# DSO_ADC.net
KiCad netlist of a schematic drawn in Altium Designer
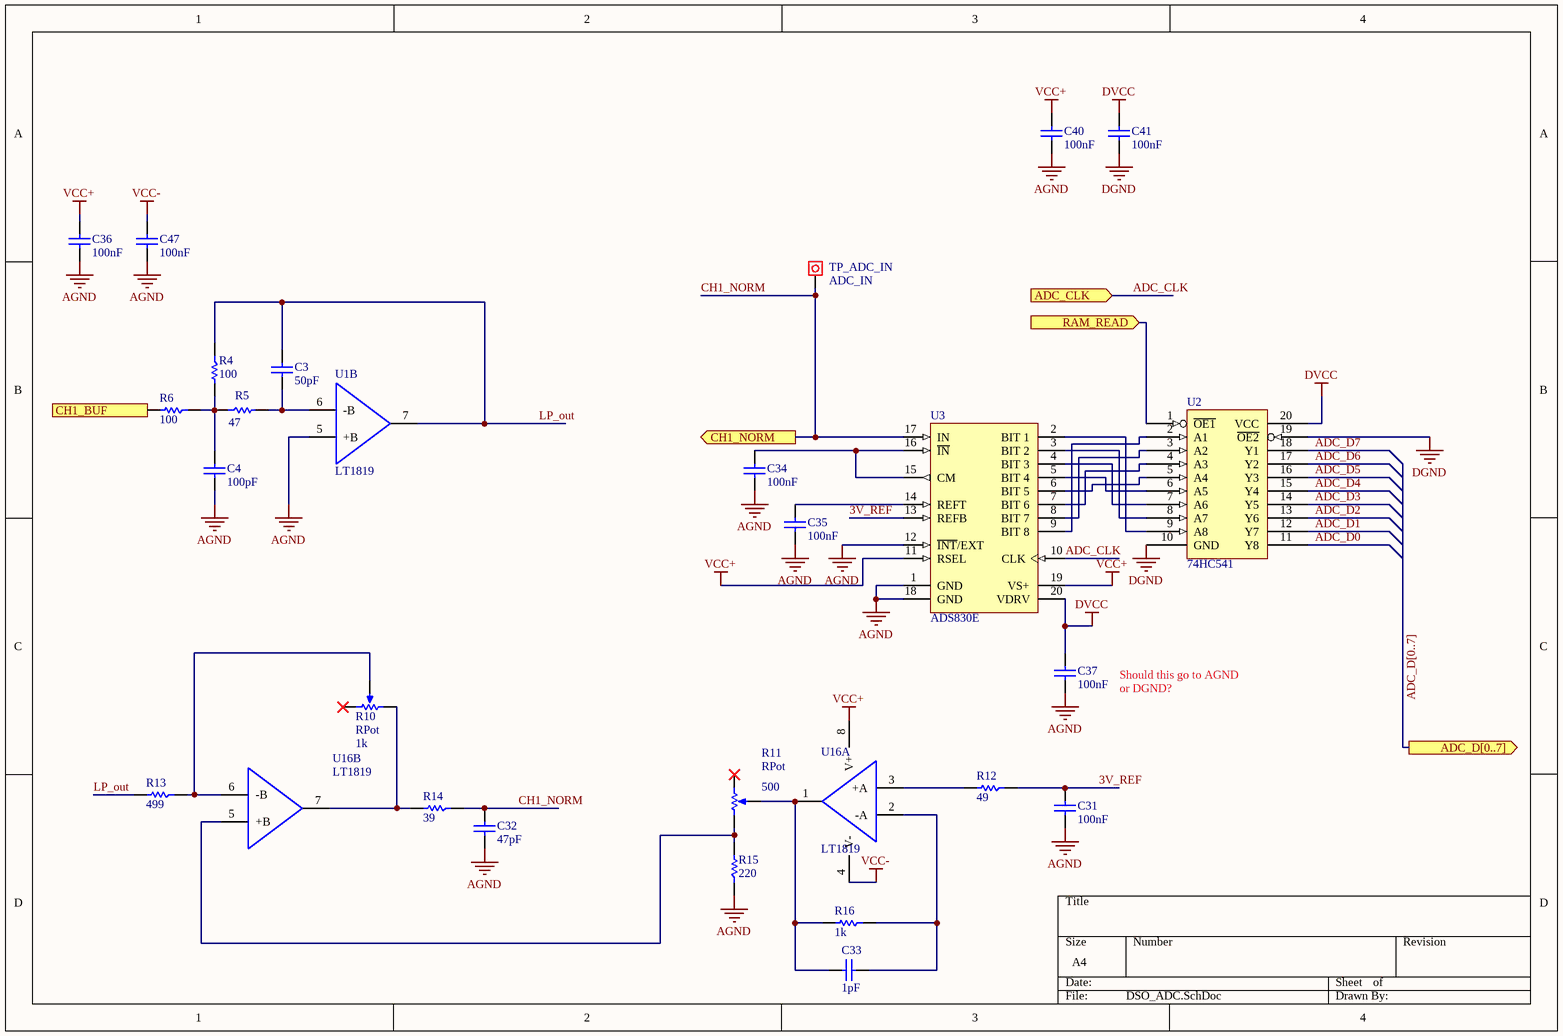
[diagram p0: DSO_ADC.SchDoc]

(export (version "E")
  (design (tool "Eeschema 10.0.6"))
  (components
    (comp (ref "C3")
      (value "50pF")
      (footprint "0805C")
      (description "Capacitor")
      (fields (field (name "REVIEWED BY") "RM - 2018/08/05"))
      (libsource (lib "DSO") (part "C"))
    )
    (comp (ref "C4")
      (value "100pF")
      (footprint "0805C")
      (description "Capacitor")
      (fields (field (name "REVIEWED BY") "RM - 2018/08/05"))
      (libsource (lib "DSO") (part "C"))
    )
    (comp (ref "C31")
      (value "100nF")
      (footprint "0805C")
      (description "Capacitor")
      (fields (field (name "REVIEWED BY") "RM - 2018/08/05"))
      (libsource (lib "DSO") (part "C"))
    )
    (comp (ref "C32")
      (value "47pF")
      (footprint "0805C")
      (description "Capacitor")
      (fields (field (name "REVIEWED BY") "RM - 2018/08/05"))
      (libsource (lib "DSO") (part "C"))
    )
    (comp (ref "C33")
      (value "1pF")
      (footprint "0805C")
      (description "Capacitor")
      (fields (field (name "REVIEWED BY") "RM - 2018/08/05"))
      (libsource (lib "DSO") (part "C"))
    )
    (comp (ref "C34")
      (value "100nF")
      (footprint "0805C")
      (description "Capacitor")
      (fields (field (name "REVIEWED BY") "RM - 2018/08/05"))
      (libsource (lib "DSO") (part "C"))
    )
    (comp (ref "C35")
      (value "100nF")
      (footprint "0805C")
      (description "Capacitor")
      (fields (field (name "REVIEWED BY") "RM - 2018/08/05"))
      (libsource (lib "DSO") (part "C"))
    )
    (comp (ref "C36")
      (value "100nF")
      (footprint "0805C")
      (description "Capacitor")
      (fields (field (name "REVIEWED BY") "RM - 2018/08/05"))
      (libsource (lib "DSO") (part "C"))
    )
    (comp (ref "C37")
      (value "100nF")
      (footprint "0805C")
      (description "Capacitor")
      (fields (field (name "REVIEWED BY") "RM - 2018/08/05"))
      (libsource (lib "DSO") (part "C"))
    )
    (comp (ref "C40")
      (value "100nF")
      (footprint "0805C")
      (description "Capacitor")
      (fields (field (name "REVIEWED BY") "RM - 2018/08/05"))
      (libsource (lib "DSO") (part "C"))
    )
    (comp (ref "C41")
      (value "100nF")
      (footprint "0805C")
      (description "Capacitor")
      (fields (field (name "REVIEWED BY") "RM - 2018/08/05"))
      (libsource (lib "DSO") (part "C"))
    )
    (comp (ref "C47")
      (value "100nF")
      (footprint "0805C")
      (description "Capacitor")
      (fields (field (name "REVIEWED BY") "RM - 2018/08/05"))
      (libsource (lib "DSO") (part "C"))
    )
    (comp (ref "R4")
      (value "100")
      (footprint "0805")
      (description "Resistor")
      (fields (field (name "REVIEWED BY") "RM - 2018/08/05"))
      (libsource (lib "DSO") (part "R"))
    )
    (comp (ref "R5")
      (value "47")
      (footprint "0805")
      (description "Resistor")
      (fields (field (name "REVIEWED BY") "RM - 2018/08/05"))
      (libsource (lib "DSO") (part "R"))
    )
    (comp (ref "R6")
      (value "100")
      (footprint "0805")
      (description "Resistor")
      (fields (field (name "REVIEWED BY") "RM - 2018/08/05"))
      (libsource (lib "DSO") (part "R"))
    )
    (comp (ref "R10")
      (value "RPot")
      (footprint "VR5")
      (description "Potentiometer")
      (fields (field (name "ALTIUM_VALUE") "1k") (field (name "PUBLISHER") "Altium Limited"))
      (libsource (lib "DSO") (part "RPot"))
    )
    (comp (ref "R11")
      (value "RPot")
      (footprint "VR5")
      (description "Potentiometer")
      (fields (field (name "ALTIUM_VALUE") "500") (field (name "PUBLISHER") "Altium Limited"))
      (libsource (lib "DSO") (part "RPot"))
    )
    (comp (ref "R12")
      (value "49")
      (footprint "0805")
      (description "Resistor")
      (fields (field (name "REVIEWED BY") "RM - 2018/08/05"))
      (libsource (lib "DSO") (part "R"))
    )
    (comp (ref "R13")
      (value "499")
      (footprint "0805")
      (description "Resistor")
      (fields (field (name "REVIEWED BY") "RM - 2018/08/05"))
      (libsource (lib "DSO") (part "R"))
    )
    (comp (ref "R14")
      (value "39")
      (footprint "0805")
      (description "Resistor")
      (fields (field (name "REVIEWED BY") "RM - 2018/08/05"))
      (libsource (lib "DSO") (part "R"))
    )
    (comp (ref "R15")
      (value "220")
      (footprint "0805")
      (description "Resistor")
      (fields (field (name "REVIEWED BY") "RM - 2018/08/05"))
      (libsource (lib "DSO") (part "R"))
    )
    (comp (ref "R16")
      (value "1k")
      (footprint "0805")
      (description "Resistor")
      (fields (field (name "REVIEWED BY") "RM - 2018/08/05"))
      (libsource (lib "DSO") (part "R"))
    )
    (comp (ref "TP_ADC_IN")
      (value "ADC_IN")
      (footprint "Testpoin")
      (description "Pad")
      (fields (field (name "Comment") "INPUT"))
      (libsource (lib "DSO") (part "Test Point"))
    )
    (comp (ref "U1")
      (value "LT1819")
      (footprint "SOIC-8")
      (description "OpAmp High Frequency Dual")
      (fields (field (name "REVIEWED BY") "RM - 2018/08/05"))
      (libsource (lib "DSO") (part "LT1819"))
    )
    (comp (ref "U2")
      (value "74HC541")
      (footprint "SOT163-1_N")
      (description "(ADV) Octal Buffer, Line Driver")
      (fields (field (name "REVIEWED BY") "RM - 2018/08/05"))
      (libsource (lib "DSO") (part "74HC541"))
    )
    (comp (ref "U3")
      (value "ADS830E")
      (footprint "TI-DBQ20_L")
      (fields (field (name "REVIEWED BY") "RM - 2018/08/05"))
      (libsource (lib "DSO") (part "ADS830E"))
    )
    (comp (ref "U16")
      (value "LT1819")
      (footprint "SOIC-8")
      (description "OpAmp High Frequency Dual")
      (fields (field (name "REVIEWED BY") "RM - 2018/08/05"))
      (libsource (lib "DSO") (part "LT1819"))
    )
  )
  (nets
    (net (code "1") (name "/3V_REF") (class "Default")
      (node (ref "C31") (pin "1") (pinfunction "1_1") (pintype "passive"))
      (node (ref "R12") (pin "1") (pintype "passive"))
      (node (ref "U3") (pin "13") (pinfunction "REFB_13") (pintype "input"))
    )
    (net (code "2") (name "/ADC_CLK") (class "Default")
      (node (ref "U3") (pin "10") (pinfunction "CLK_10") (pintype "input"))
    )
    (net (code "3") (name "/ADC_D0") (class "Default")
      (node (ref "U2") (pin "11") (pinfunction "Y8_11") (pintype "tri_state"))
    )
    (net (code "4") (name "/ADC_D1") (class "Default")
      (node (ref "U2") (pin "12") (pinfunction "Y7_12") (pintype "tri_state"))
    )
    (net (code "5") (name "/ADC_D2") (class "Default")
      (node (ref "U2") (pin "13") (pinfunction "Y6_13") (pintype "tri_state"))
    )
    (net (code "6") (name "/ADC_D3") (class "Default")
      (node (ref "U2") (pin "14") (pinfunction "Y5_14") (pintype "tri_state"))
    )
    (net (code "7") (name "/ADC_D4") (class "Default")
      (node (ref "U2") (pin "15") (pinfunction "Y4_15") (pintype "tri_state"))
    )
    (net (code "8") (name "/ADC_D5") (class "Default")
      (node (ref "U2") (pin "16") (pinfunction "Y3_16") (pintype "tri_state"))
    )
    (net (code "9") (name "/ADC_D6") (class "Default")
      (node (ref "U2") (pin "17") (pinfunction "Y2_17") (pintype "tri_state"))
    )
    (net (code "10") (name "/ADC_D7") (class "Default")
      (node (ref "U2") (pin "18") (pinfunction "Y1_18") (pintype "tri_state"))
    )
    (net (code "12") (name "/CH1_BUF") (class "Default") (node (ref "R6") (pin "2") (pintype "passive")))
    (net (code "13") (name "/CH1_NORM") (class "Default")
      (node (ref "C32") (pin "1") (pinfunction "1_1") (pintype "passive"))
      (node (ref "R14") (pin "1") (pintype "passive"))
      (node (ref "TP_ADC_IN") (pin "1") (pintype "passive"))
      (node (ref "U3") (pin "17") (pinfunction "IN_17") (pintype "input"))
    )
    (net (code "14") (name "/LP_out") (class "Default")
      (node (ref "C3") (pin "1") (pinfunction "1_1") (pintype "passive"))
      (node (ref "R13") (pin "2") (pintype "passive"))
      (node (ref "R4") (pin "1") (pintype "passive"))
      (node (ref "U1") (pin "7") (pinfunction "OUTB_7") (pintype "passive"))
    )
    (net (code "15") (name "/RAM_READ") (class "Default")
      (node (ref "U2") (pin "1") (pinfunction "~{OE1}_1") (pintype "input"))
    )
    (net (code "16") (name "AGND") (class "Default")
      (node (ref "C31") (pin "2") (pinfunction "2_2") (pintype "passive"))
      (node (ref "C32") (pin "2") (pinfunction "2_2") (pintype "passive"))
      (node (ref "C34") (pin "2") (pinfunction "2_2") (pintype "passive"))
      (node (ref "C35") (pin "2") (pinfunction "2_2") (pintype "passive"))
      (node (ref "C36") (pin "2") (pinfunction "2_2") (pintype "passive"))
      (node (ref "C37") (pin "1") (pinfunction "1_1") (pintype "passive"))
      (node (ref "C4") (pin "2") (pinfunction "2_2") (pintype "passive"))
      (node (ref "C40") (pin "2") (pinfunction "2_2") (pintype "passive"))
      (node (ref "C47") (pin "2") (pinfunction "2_2") (pintype "passive"))
      (node (ref "R15") (pin "1") (pintype "passive"))
      (node (ref "U1") (pin "5") (pinfunction "+B_5") (pintype "passive"))
      (node (ref "U3") (pin "1") (pinfunction "GND_1") (pintype "power_in"))
      (node (ref "U3") (pin "12") (pinfunction "~{INT}/EXT_12") (pintype "input"))
      (node (ref "U3") (pin "18") (pinfunction "GND_18") (pintype "power_in"))
    )
    (net (code "17") (name "DGND") (class "Default")
      (node (ref "C41") (pin "2") (pinfunction "2_2") (pintype "passive"))
      (node (ref "U2") (pin "10") (pinfunction "GND_10") (pintype "power_in"))
      (node (ref "U2") (pin "19") (pinfunction "~{OE2}_19") (pintype "input"))
    )
    (net (code "18") (name "DVCC") (class "Default")
      (node (ref "C37") (pin "2") (pinfunction "2_2") (pintype "passive"))
      (node (ref "C41") (pin "1") (pinfunction "1_1") (pintype "passive"))
      (node (ref "U2") (pin "20") (pinfunction "VCC_20") (pintype "power_in"))
      (node (ref "U3") (pin "20") (pinfunction "VDRV_20") (pintype "power_in"))
    )
    (net (code "19") (name "Net-(C4-Pad1)") (class "Default")
      (node (ref "C4") (pin "1") (pinfunction "1_1") (pintype "passive"))
      (node (ref "R4") (pin "2") (pintype "passive"))
      (node (ref "R5") (pin "1") (pintype "passive"))
      (node (ref "R6") (pin "1") (pintype "passive"))
    )
    (net (code "20") (name "Net-(R10-TAP)") (class "Default")
      (node (ref "R10") (pin "2") (pinfunction "TAP_2") (pintype "passive"))
      (node (ref "R13") (pin "1") (pintype "passive"))
      (node (ref "U16") (pin "6") (pinfunction "-B_6") (pintype "passive"))
    )
    (net (code "21") (name "Net-(R10-TOP)") (class "Default")
      (node (ref "R10") (pin "1") (pinfunction "TOP_1") (pintype "passive"))
      (node (ref "R14") (pin "2") (pintype "passive"))
      (node (ref "U16") (pin "7") (pinfunction "OUTB_7") (pintype "passive"))
    )
    (net (code "22") (name "Net-(R11-TAP)") (class "Default")
      (node (ref "C33") (pin "2") (pinfunction "2_2") (pintype "passive"))
      (node (ref "R11") (pin "2") (pinfunction "TAP_2") (pintype "passive"))
      (node (ref "R16") (pin "2") (pintype "passive"))
      (node (ref "U16") (pin "1") (pinfunction "OUTA_1") (pintype "passive"))
    )
    (net (code "23") (name "Net-(R11-TOP)") (class "Default")
      (node (ref "R11") (pin "1") (pinfunction "TOP_1") (pintype "passive"))
      (node (ref "R15") (pin "2") (pintype "passive"))
      (node (ref "U16") (pin "5") (pinfunction "+B_5") (pintype "passive"))
    )
    (net (code "24") (name "Net-(U1B--B)") (class "Default")
      (node (ref "C3") (pin "2") (pinfunction "2_2") (pintype "passive"))
      (node (ref "R5") (pin "2") (pintype "passive"))
      (node (ref "U1") (pin "6") (pinfunction "-B_6") (pintype "passive"))
    )
    (net (code "25") (name "Net-(U2-A1)") (class "Default")
      (node (ref "U2") (pin "2") (pinfunction "A1_2") (pintype "input"))
      (node (ref "U3") (pin "9") (pinfunction "BIT_8_9") (pintype "tri_state"))
    )
    (net (code "26") (name "Net-(U2-A2)") (class "Default")
      (node (ref "U2") (pin "3") (pinfunction "A2_3") (pintype "input"))
      (node (ref "U3") (pin "8") (pinfunction "BIT_7_8") (pintype "tri_state"))
    )
    (net (code "27") (name "Net-(U2-A3)") (class "Default")
      (node (ref "U2") (pin "4") (pinfunction "A3_4") (pintype "input"))
      (node (ref "U3") (pin "7") (pinfunction "BIT_6_7") (pintype "tri_state"))
    )
    (net (code "28") (name "Net-(U2-A4)") (class "Default")
      (node (ref "U2") (pin "5") (pinfunction "A4_5") (pintype "input"))
      (node (ref "U3") (pin "6") (pinfunction "BIT_5_6") (pintype "tri_state"))
    )
    (net (code "29") (name "Net-(U2-A5)") (class "Default")
      (node (ref "U2") (pin "6") (pinfunction "A5_6") (pintype "input"))
      (node (ref "U3") (pin "5") (pinfunction "BIT_4_5") (pintype "tri_state"))
    )
    (net (code "30") (name "Net-(U2-A6)") (class "Default")
      (node (ref "U2") (pin "7") (pinfunction "A6_7") (pintype "input"))
      (node (ref "U3") (pin "4") (pinfunction "BIT_3_4") (pintype "tri_state"))
    )
    (net (code "31") (name "Net-(U2-A7)") (class "Default")
      (node (ref "U2") (pin "8") (pinfunction "A7_8") (pintype "input"))
      (node (ref "U3") (pin "3") (pinfunction "BIT_2_3") (pintype "tri_state"))
    )
    (net (code "32") (name "Net-(U2-A8)") (class "Default")
      (node (ref "U2") (pin "9") (pinfunction "A8_9") (pintype "input"))
      (node (ref "U3") (pin "2") (pinfunction "BIT_1_2") (pintype "tri_state"))
    )
    (net (code "33") (name "Net-(U3-CM)") (class "Default")
      (node (ref "C34") (pin "1") (pinfunction "1_1") (pintype "passive"))
      (node (ref "U3") (pin "15") (pinfunction "CM_15") (pintype "output"))
      (node (ref "U3") (pin "16") (pinfunction "~{IN}_16") (pintype "input"))
    )
    (net (code "34") (name "Net-(U3-REFT)") (class "Default")
      (node (ref "C35") (pin "1") (pinfunction "1_1") (pintype "passive"))
      (node (ref "U3") (pin "14") (pinfunction "REFT_14") (pintype "input"))
    )
    (net (code "35") (name "Net-(U16A-+A)") (class "Default")
      (node (ref "R12") (pin "2") (pintype "passive"))
      (node (ref "U16") (pin "3") (pinfunction "+A_3") (pintype "passive"))
    )
    (net (code "36") (name "Net-(U16A--A)") (class "Default")
      (node (ref "C33") (pin "1") (pinfunction "1_1") (pintype "passive"))
      (node (ref "R16") (pin "1") (pintype "passive"))
      (node (ref "U16") (pin "2") (pinfunction "-A_2") (pintype "passive"))
    )
    (net (code "37") (name "VCC+") (class "Default")
      (node (ref "C36") (pin "1") (pinfunction "1_1") (pintype "passive"))
      (node (ref "C40") (pin "1") (pinfunction "1_1") (pintype "passive"))
      (node (ref "U16") (pin "8") (pinfunction "V+_8") (pintype "passive"))
      (node (ref "U3") (pin "11") (pinfunction "RSEL_11") (pintype "input"))
      (node (ref "U3") (pin "19") (pinfunction "VS+_19") (pintype "power_in"))
    )
    (net (code "38") (name "VCC-") (class "Default")
      (node (ref "C47") (pin "1") (pinfunction "1_1") (pintype "passive"))
      (node (ref "U16") (pin "4") (pinfunction "V-_4") (pintype "passive"))
    )
    (net (code "39") (name "unconnected-(R10-BOT-Pad3)") (class "Default")
      (node (ref "R10") (pin "3") (pinfunction "BOT_3") (pintype "passive+no_connect"))
    )
    (net (code "40") (name "unconnected-(R11-BOT-Pad3)") (class "Default")
      (node (ref "R11") (pin "3") (pinfunction "BOT_3") (pintype "passive+no_connect"))
    )
  )
)
